# 4_95.net
KiCad netlist of a schematic drawn in EasyEDA
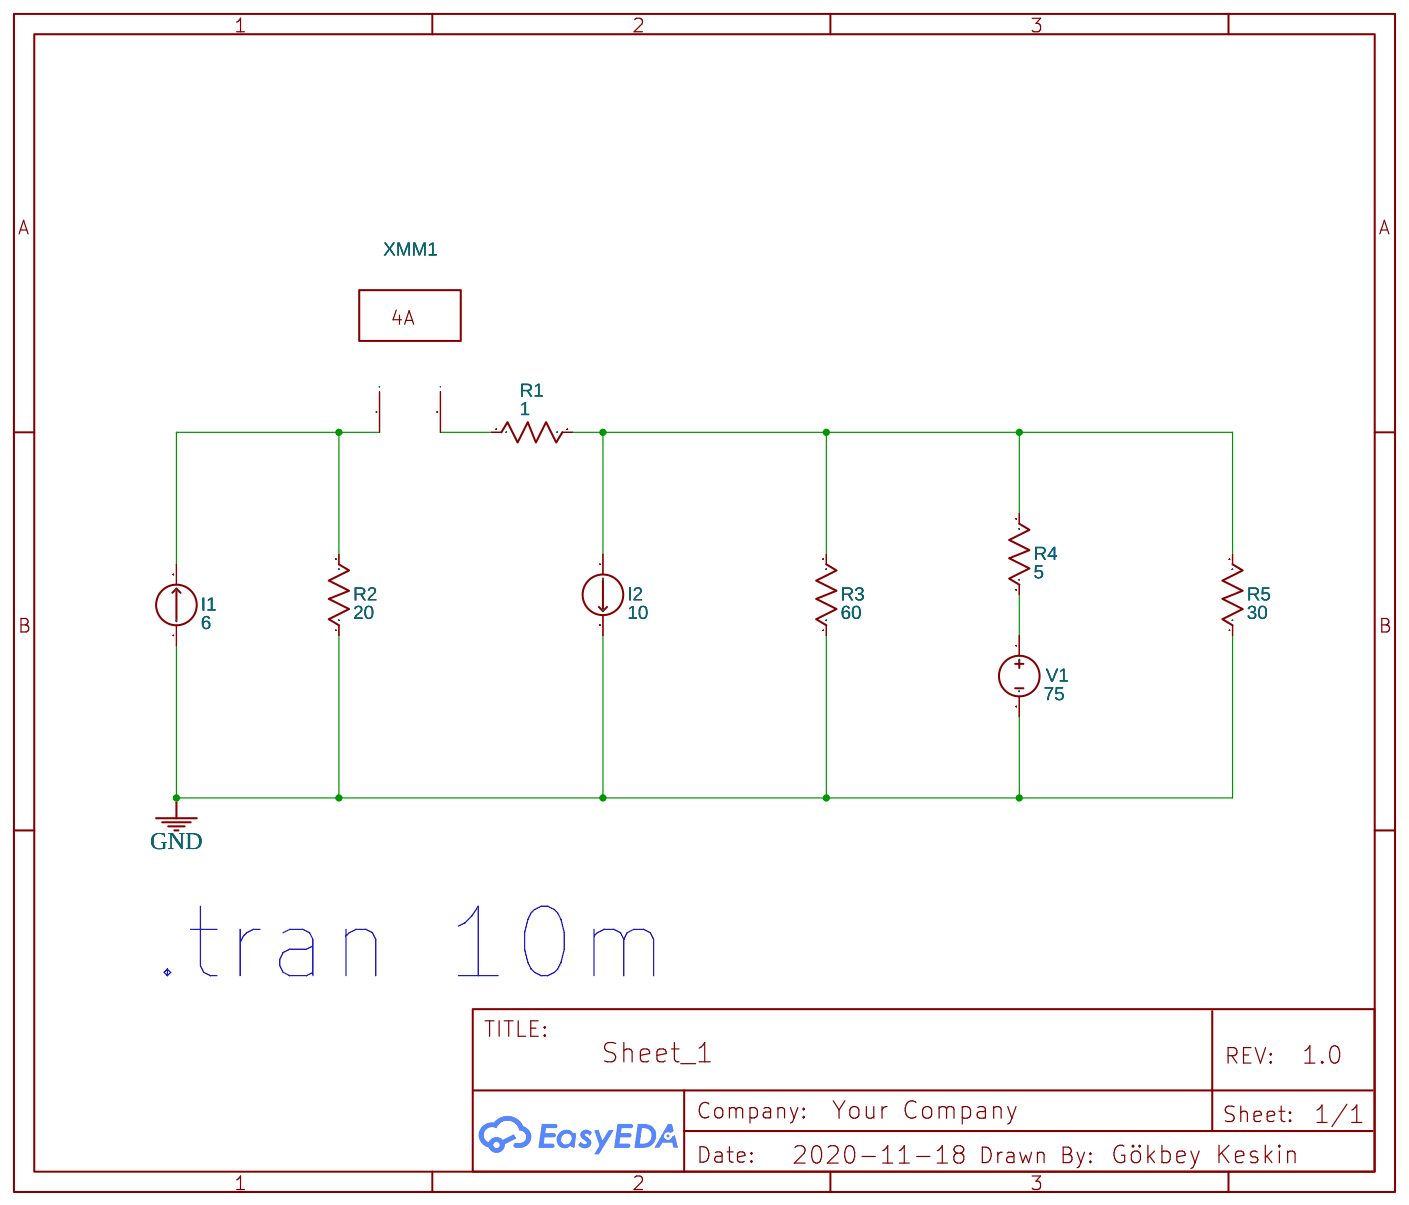
[diagram p0: schematic sheet]

(export (version "E")
  (design (tool "Eeschema 10.0.6"))
  (components
    (comp (ref "I1") (value "6") (libsource (lib "") (part "IDC")))
    (comp (ref "I2") (value "10") (libsource (lib "") (part "IDC_1")))
    (comp (ref "R1") (value "1") (libsource (lib "") (part "Resistor_US_1")))
    (comp (ref "R2") (value "20") (libsource (lib "") (part "Resistor_US")))
    (comp (ref "R3") (value "60") (libsource (lib "") (part "Resistor_US")))
    (comp (ref "R4") (value "5") (libsource (lib "") (part "Resistor_US")))
    (comp (ref "R5") (value "30") (libsource (lib "") (part "Resistor_US")))
    (comp (ref "V1") (value "75") (libsource (lib "") (part "VDC")))
    (comp (ref "XMM1") (value "Multimeter") (libsource (lib "") (part "MULTIMETER")))
  )
  (nets
    (net (code "1") (name "GND") (class "Default")
      (node (ref "I1") (pin "1") (pinfunction "1_1") (pintype "unspecified"))
      (node (ref "I2") (pin "2") (pinfunction "2_2") (pintype "unspecified"))
      (node (ref "R2") (pin "1") (pinfunction "1_1") (pintype "unspecified"))
      (node (ref "R3") (pin "1") (pinfunction "1_1") (pintype "unspecified"))
      (node (ref "R5") (pin "1") (pinfunction "1_1") (pintype "unspecified"))
      (node (ref "V1") (pin "2") (pinfunction "2_2") (pintype "unspecified"))
    )
    (net (code "2") (name "Net-(I2-Pad1)") (class "Default")
      (node (ref "I2") (pin "1") (pinfunction "1_1") (pintype "unspecified"))
      (node (ref "R1") (pin "2") (pinfunction "2_2") (pintype "unspecified"))
      (node (ref "R3") (pin "2") (pinfunction "2_2") (pintype "unspecified"))
      (node (ref "R4") (pin "2") (pinfunction "2_2") (pintype "unspecified"))
      (node (ref "R5") (pin "2") (pinfunction "2_2") (pintype "unspecified"))
    )
    (net (code "3") (name "Net-(R4-Pad1)") (class "Default")
      (node (ref "R4") (pin "1") (pinfunction "1_1") (pintype "unspecified"))
      (node (ref "V1") (pin "1") (pinfunction "1_1") (pintype "unspecified"))
    )
    (net (code "4") (name "Net-(XMM1-+)") (class "Default")
      (node (ref "I1") (pin "2") (pinfunction "2_2") (pintype "unspecified"))
      (node (ref "R2") (pin "2") (pinfunction "2_2") (pintype "unspecified"))
      (node (ref "XMM1") (pin "1") (pinfunction "+_1") (pintype "unspecified"))
    )
    (net (code "5") (name "Net-(XMM1-I)") (class "Default")
      (node (ref "R1") (pin "1") (pinfunction "1_1") (pintype "unspecified"))
      (node (ref "XMM1") (pin "2") (pinfunction "I_2") (pintype "unspecified"))
    )
  )
)
